# StickSoc_Right.net
KiCad netlist of a schematic drawn in EAGLE
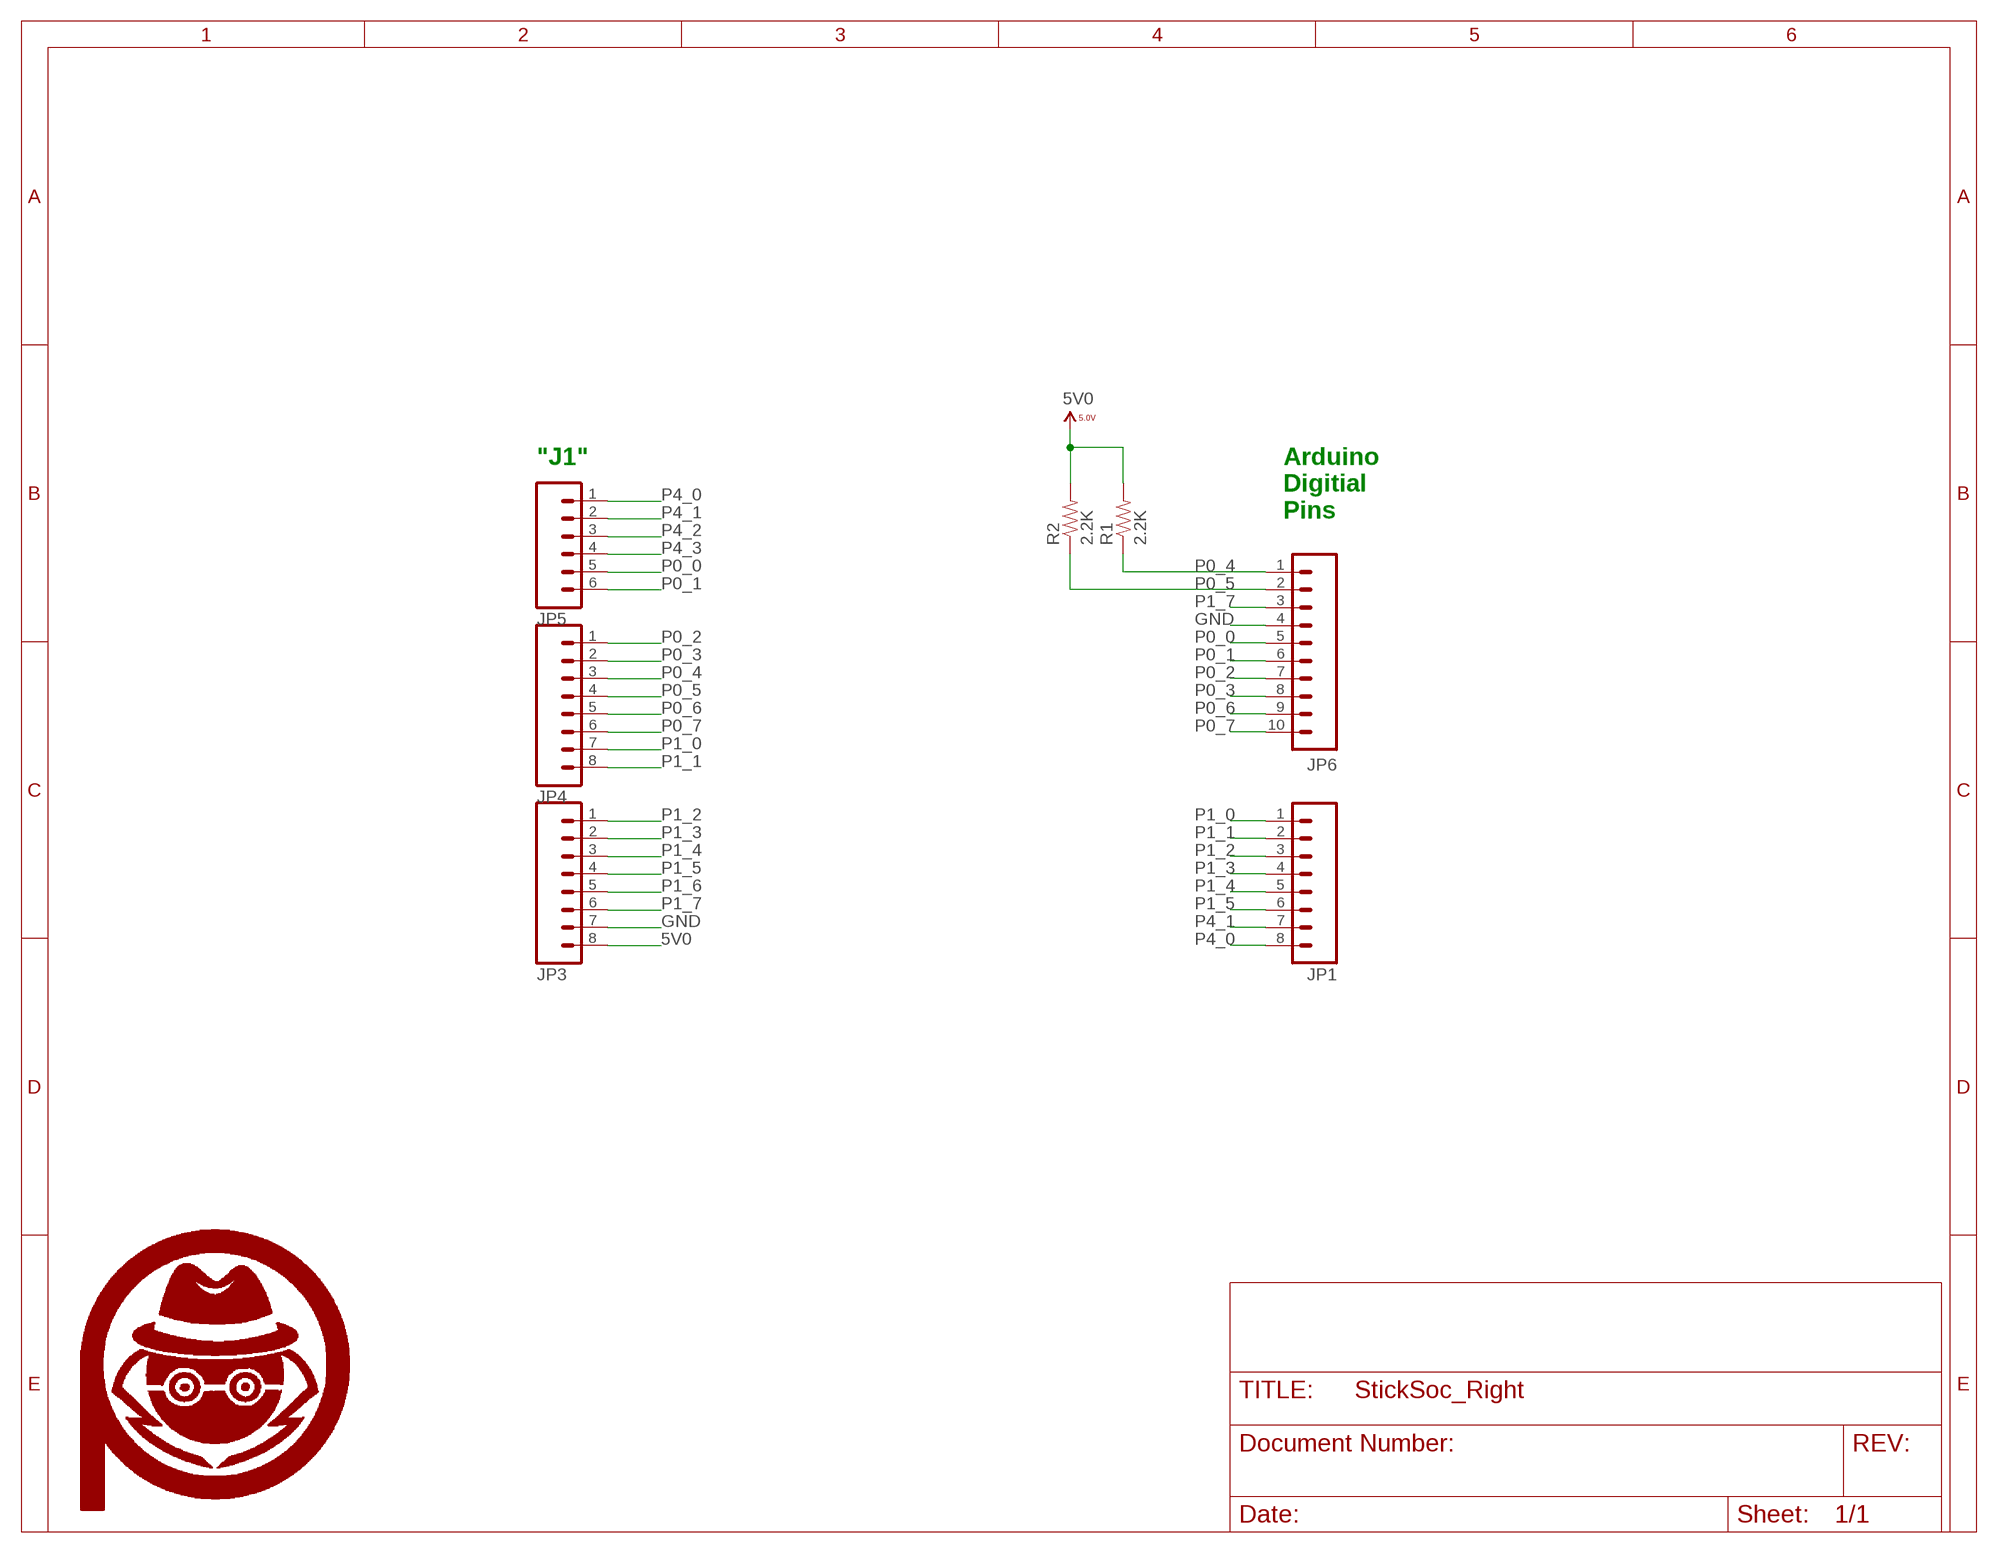
[diagram p0: schematic, sheet 1]

(export (version "E")
  (design (tool "Eeschema 10.0.6"))
  (components
    (comp (ref "JP1")
      (value "M081X08")
      (footprint "eagle-import:1X08")
      (libsource (lib "eagle-import") (part "M081X08"))
    )
    (comp (ref "JP3")
      (value "M081X08")
      (footprint "eagle-import:1X08")
      (libsource (lib "eagle-import") (part "M081X08"))
    )
    (comp (ref "JP4")
      (value "M081X08")
      (footprint "eagle-import:1X08")
      (libsource (lib "eagle-import") (part "M081X08"))
    )
    (comp (ref "JP5")
      (value "M06SIP")
      (footprint "eagle-import:1X06")
      (libsource (lib "eagle-import") (part "M06SIP"))
    )
    (comp (ref "JP6")
      (value "M10SILK_FEMALE_PTH")
      (footprint "eagle-import:1X10")
      (libsource (lib "eagle-import") (part "M10SILK_FEMALE_PTH"))
    )
    (comp (ref "R1")
      (value "2.2K")
      (footprint "eagle-import:0805")
      (libsource (lib "eagle-import") (part "RESISTOR0805-RES"))
    )
    (comp (ref "R2")
      (value "2.2K")
      (footprint "eagle-import:0805")
      (libsource (lib "eagle-import") (part "RESISTOR0805-RES"))
    )
    (comp (ref "U$1")
      (value "PA_LOGO_SYMSMALL")
      (footprint "eagle-import:PA_LOGO_AGENT_SMALL_SYM")
      (libsource (lib "eagle-import") (part "PA_LOGO_SYMSMALL"))
    )
    (comp (ref "U$2")
      (value "PA_LOGO_SYMSMALL")
      (footprint "eagle-import:PA_LOGO_AGENT_SMALL_SYM")
      (libsource (lib "eagle-import") (part "PA_LOGO_SYMSMALL"))
    )
  )
  (nets
    (net (code "1") (name "/GND") (class "Default")
      (node (ref "JP3") (pin "7") (pinfunction "7_7") (pintype "passive"))
      (node (ref "JP6") (pin "4") (pinfunction "4_4") (pintype "passive"))
    )
    (net (code "2") (name "/P0_0") (class "Default")
      (node (ref "JP5") (pin "5") (pinfunction "5_5") (pintype "passive"))
      (node (ref "JP6") (pin "5") (pinfunction "5_5") (pintype "passive"))
    )
    (net (code "3") (name "/P0_1") (class "Default")
      (node (ref "JP5") (pin "6") (pinfunction "6_6") (pintype "passive"))
      (node (ref "JP6") (pin "6") (pinfunction "6_6") (pintype "passive"))
    )
    (net (code "4") (name "/P0_2") (class "Default")
      (node (ref "JP4") (pin "1") (pinfunction "1_1") (pintype "passive"))
      (node (ref "JP6") (pin "7") (pinfunction "7_7") (pintype "passive"))
    )
    (net (code "5") (name "/P0_3") (class "Default")
      (node (ref "JP4") (pin "2") (pinfunction "2_2") (pintype "passive"))
      (node (ref "JP6") (pin "8") (pinfunction "8_8") (pintype "passive"))
    )
    (net (code "6") (name "/P0_4") (class "Default")
      (node (ref "JP4") (pin "3") (pinfunction "3_3") (pintype "passive"))
      (node (ref "JP6") (pin "1") (pinfunction "1_1") (pintype "passive"))
      (node (ref "R1") (pin "1") (pinfunction "1_1") (pintype "passive"))
    )
    (net (code "7") (name "/P0_5") (class "Default")
      (node (ref "JP4") (pin "4") (pinfunction "4_4") (pintype "passive"))
      (node (ref "JP6") (pin "2") (pinfunction "2_2") (pintype "passive"))
      (node (ref "R2") (pin "1") (pinfunction "1_1") (pintype "passive"))
    )
    (net (code "8") (name "/P0_6") (class "Default")
      (node (ref "JP4") (pin "5") (pinfunction "5_5") (pintype "passive"))
      (node (ref "JP6") (pin "9") (pinfunction "9_9") (pintype "passive"))
    )
    (net (code "9") (name "/P0_7") (class "Default")
      (node (ref "JP4") (pin "6") (pinfunction "6_6") (pintype "passive"))
      (node (ref "JP6") (pin "10") (pinfunction "10_10") (pintype "passive"))
    )
    (net (code "10") (name "/P1_0") (class "Default")
      (node (ref "JP1") (pin "1") (pinfunction "1_1") (pintype "passive"))
      (node (ref "JP4") (pin "7") (pinfunction "7_7") (pintype "passive"))
    )
    (net (code "11") (name "/P1_1") (class "Default")
      (node (ref "JP1") (pin "2") (pinfunction "2_2") (pintype "passive"))
      (node (ref "JP4") (pin "8") (pinfunction "8_8") (pintype "passive"))
    )
    (net (code "12") (name "/P1_2") (class "Default")
      (node (ref "JP1") (pin "3") (pinfunction "3_3") (pintype "passive"))
      (node (ref "JP3") (pin "1") (pinfunction "1_1") (pintype "passive"))
    )
    (net (code "13") (name "/P1_3") (class "Default")
      (node (ref "JP1") (pin "4") (pinfunction "4_4") (pintype "passive"))
      (node (ref "JP3") (pin "2") (pinfunction "2_2") (pintype "passive"))
    )
    (net (code "14") (name "/P1_4") (class "Default")
      (node (ref "JP1") (pin "5") (pinfunction "5_5") (pintype "passive"))
      (node (ref "JP3") (pin "3") (pinfunction "3_3") (pintype "passive"))
    )
    (net (code "15") (name "/P1_5") (class "Default")
      (node (ref "JP1") (pin "6") (pinfunction "6_6") (pintype "passive"))
      (node (ref "JP3") (pin "4") (pinfunction "4_4") (pintype "passive"))
    )
    (net (code "16") (name "/P1_6") (class "Default")
      (node (ref "JP3") (pin "5") (pinfunction "5_5") (pintype "passive"))
    )
    (net (code "17") (name "/P1_7") (class "Default")
      (node (ref "JP3") (pin "6") (pinfunction "6_6") (pintype "passive"))
      (node (ref "JP6") (pin "3") (pinfunction "3_3") (pintype "passive"))
    )
    (net (code "18") (name "/P4_0") (class "Default")
      (node (ref "JP1") (pin "8") (pinfunction "8_8") (pintype "passive"))
      (node (ref "JP5") (pin "1") (pinfunction "1_1") (pintype "passive"))
    )
    (net (code "19") (name "/P4_1") (class "Default")
      (node (ref "JP1") (pin "7") (pinfunction "7_7") (pintype "passive"))
      (node (ref "JP5") (pin "2") (pinfunction "2_2") (pintype "passive"))
    )
    (net (code "20") (name "/P4_2") (class "Default")
      (node (ref "JP5") (pin "3") (pinfunction "3_3") (pintype "passive"))
    )
    (net (code "21") (name "/P4_3") (class "Default")
      (node (ref "JP5") (pin "4") (pinfunction "4_4") (pintype "passive"))
    )
    (net (code "22") (name "5V0") (class "Default")
      (node (ref "JP3") (pin "8") (pinfunction "8_8") (pintype "passive"))
      (node (ref "R1") (pin "2") (pinfunction "2_2") (pintype "passive"))
      (node (ref "R2") (pin "2") (pinfunction "2_2") (pintype "passive"))
    )
  )
)
